# untitled.net
KiCad netlist of a schematic drawn in EAGLE
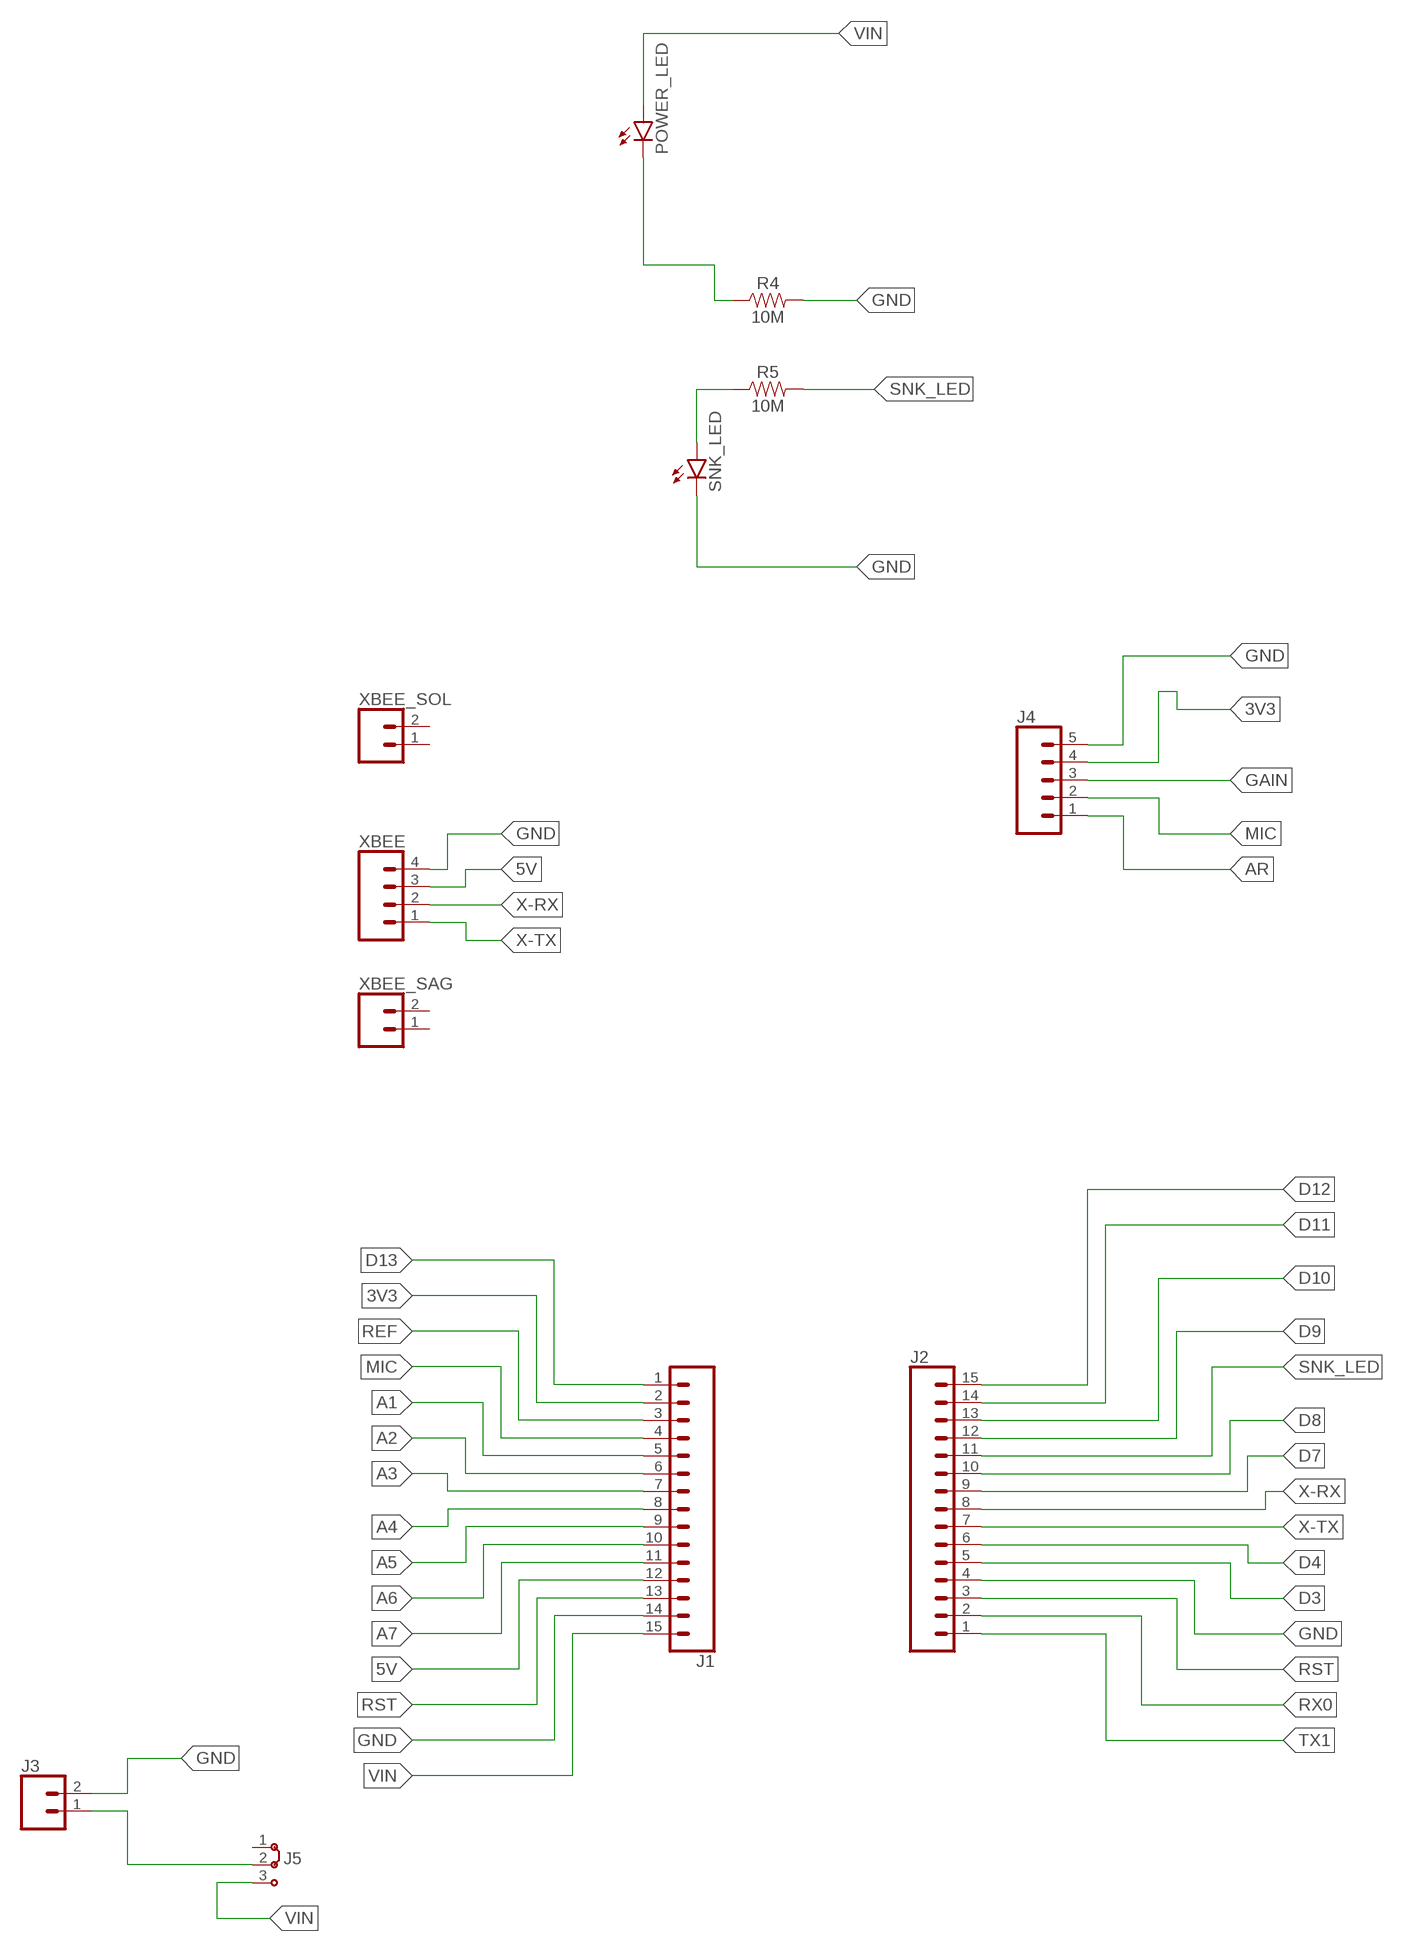
[diagram p0: schematic, sheet 1]

(export (version "E")
  (design (tool "Eeschema 10.0.6"))
  (components
    (comp (ref "J1")
      (value "CONN_15")
      (footprint "eagle-import:1X15")
      (libsource (lib "eagle-import") (part "CONN_15"))
    )
    (comp (ref "J2")
      (value "CONN_15")
      (footprint "eagle-import:1X15")
      (libsource (lib "eagle-import") (part "CONN_15"))
    )
    (comp (ref "J3")
      (value "CONN_025MM")
      (footprint "eagle-import:SCREWTERMINAL-5MM-2")
      (libsource (lib "eagle-import") (part "CONN_025MM"))
    )
    (comp (ref "J4")
      (value "CONN_05")
      (footprint "eagle-import:1X05")
      (libsource (lib "eagle-import") (part "CONN_05"))
    )
    (comp (ref "J5")
      (value "J2X2MM")
      (footprint "eagle-import:04C")
      (libsource (lib "eagle-import") (part "J2X2MM"))
    )
    (comp (ref "POWER_LED")
      (value "LED5MM")
      (footprint "eagle-import:LED5MM")
      (libsource (lib "eagle-import") (part "LED5MM"))
    )
    (comp (ref "R4")
      (value "10M")
      (footprint "eagle-import:AXIAL-0.3")
      (libsource (lib "eagle-import") (part "10MOHM-HORIZ-1/4W-5%"))
    )
    (comp (ref "R5")
      (value "10M")
      (footprint "eagle-import:AXIAL-0.3")
      (libsource (lib "eagle-import") (part "10MOHM-HORIZ-1/4W-5%"))
    )
    (comp (ref "SNK_LED")
      (value "LED5MM")
      (footprint "eagle-import:LED5MM")
      (libsource (lib "eagle-import") (part "LED5MM"))
    )
    (comp (ref "XBEE")
      (value "CONN_04")
      (footprint "eagle-import:1X04")
      (libsource (lib "eagle-import") (part "CONN_04"))
    )
    (comp (ref "XBEE_SAG")
      (value "CONN_02")
      (footprint "eagle-import:1X02")
      (libsource (lib "eagle-import") (part "CONN_02"))
    )
    (comp (ref "XBEE_SOL")
      (value "CONN_02")
      (footprint "eagle-import:1X02")
      (libsource (lib "eagle-import") (part "CONN_02"))
    )
  )
  (nets
    (net (code "1") (name "3V3") (class "Default")
      (node (ref "J1") (pin "2") (pinfunction "2_2") (pintype "passive"))
      (node (ref "J4") (pin "4") (pinfunction "4_4") (pintype "passive"))
    )
    (net (code "2") (name "5V") (class "Default")
      (node (ref "J1") (pin "12") (pinfunction "12_12") (pintype "passive"))
      (node (ref "XBEE") (pin "3") (pinfunction "3_3") (pintype "passive"))
    )
    (net (code "3") (name "A1") (class "Default")
      (node (ref "J1") (pin "5") (pinfunction "5_5") (pintype "passive"))
    )
    (net (code "4") (name "A2") (class "Default")
      (node (ref "J1") (pin "6") (pinfunction "6_6") (pintype "passive"))
    )
    (net (code "5") (name "A3") (class "Default")
      (node (ref "J1") (pin "7") (pinfunction "7_7") (pintype "passive"))
    )
    (net (code "6") (name "A4") (class "Default")
      (node (ref "J1") (pin "8") (pinfunction "8_8") (pintype "passive"))
    )
    (net (code "7") (name "A5") (class "Default")
      (node (ref "J1") (pin "9") (pinfunction "9_9") (pintype "passive"))
    )
    (net (code "8") (name "A6") (class "Default")
      (node (ref "J1") (pin "10") (pinfunction "10_10") (pintype "passive"))
    )
    (net (code "9") (name "A7") (class "Default")
      (node (ref "J1") (pin "11") (pinfunction "11_11") (pintype "passive"))
    )
    (net (code "10") (name "AR") (class "Default")
      (node (ref "J4") (pin "1") (pinfunction "1_1") (pintype "passive"))
    )
    (net (code "11") (name "D3") (class "Default")
      (node (ref "J2") (pin "5") (pinfunction "5_5") (pintype "passive"))
    )
    (net (code "12") (name "D4") (class "Default")
      (node (ref "J2") (pin "6") (pinfunction "6_6") (pintype "passive"))
    )
    (net (code "13") (name "D7") (class "Default")
      (node (ref "J2") (pin "9") (pinfunction "9_9") (pintype "passive"))
    )
    (net (code "14") (name "D8") (class "Default")
      (node (ref "J2") (pin "10") (pinfunction "10_10") (pintype "passive"))
    )
    (net (code "15") (name "D9") (class "Default")
      (node (ref "J2") (pin "12") (pinfunction "12_12") (pintype "passive"))
    )
    (net (code "16") (name "D10") (class "Default")
      (node (ref "J2") (pin "13") (pinfunction "13_13") (pintype "passive"))
    )
    (net (code "17") (name "D11") (class "Default")
      (node (ref "J2") (pin "14") (pinfunction "14_14") (pintype "passive"))
    )
    (net (code "18") (name "D12") (class "Default")
      (node (ref "J2") (pin "15") (pinfunction "15_15") (pintype "passive"))
    )
    (net (code "19") (name "D13") (class "Default")
      (node (ref "J1") (pin "1") (pinfunction "1_1") (pintype "passive"))
    )
    (net (code "20") (name "GAIN") (class "Default")
      (node (ref "J4") (pin "3") (pinfunction "3_3") (pintype "passive"))
    )
    (net (code "21") (name "GND") (class "Default")
      (node (ref "J1") (pin "14") (pinfunction "14_14") (pintype "passive"))
      (node (ref "J2") (pin "4") (pinfunction "4_4") (pintype "passive"))
      (node (ref "J3") (pin "2") (pinfunction "2_2") (pintype "passive"))
      (node (ref "J4") (pin "5") (pinfunction "5_5") (pintype "passive"))
      (node (ref "R4") (pin "P$2") (pinfunction "2_P$2") (pintype "passive"))
      (node (ref "SNK_LED") (pin "K") (pinfunction "C_K") (pintype "passive"))
      (node (ref "XBEE") (pin "4") (pinfunction "4_4") (pintype "passive"))
    )
    (net (code "22") (name "MIC") (class "Default")
      (node (ref "J1") (pin "4") (pinfunction "4_4") (pintype "passive"))
      (node (ref "J4") (pin "2") (pinfunction "2_2") (pintype "passive"))
    )
    (net (code "23") (name "Net-(J3-Pad1)") (class "Default")
      (node (ref "J3") (pin "1") (pinfunction "1_1") (pintype "passive"))
      (node (ref "J5") (pin "2") (pinfunction "2_2") (pintype "passive"))
    )
    (net (code "24") (name "Net-(POWER_LED-C)") (class "Default")
      (node (ref "POWER_LED") (pin "K") (pinfunction "C_K") (pintype "passive"))
      (node (ref "R4") (pin "P$1") (pinfunction "1_P$1") (pintype "passive"))
    )
    (net (code "25") (name "Net-(R5-1)") (class "Default")
      (node (ref "R5") (pin "P$1") (pinfunction "1_P$1") (pintype "passive"))
      (node (ref "SNK_LED") (pin "A") (pinfunction "A_A") (pintype "passive"))
    )
    (net (code "26") (name "REF") (class "Default")
      (node (ref "J1") (pin "3") (pinfunction "3_3") (pintype "passive"))
    )
    (net (code "27") (name "RST") (class "Default")
      (node (ref "J1") (pin "13") (pinfunction "13_13") (pintype "passive"))
      (node (ref "J2") (pin "3") (pinfunction "3_3") (pintype "passive"))
    )
    (net (code "28") (name "RX0") (class "Default")
      (node (ref "J2") (pin "2") (pinfunction "2_2") (pintype "passive"))
    )
    (net (code "29") (name "SNK_LED") (class "Default")
      (node (ref "J2") (pin "11") (pinfunction "11_11") (pintype "passive"))
      (node (ref "R5") (pin "P$2") (pinfunction "2_P$2") (pintype "passive"))
    )
    (net (code "30") (name "TX1") (class "Default")
      (node (ref "J2") (pin "1") (pinfunction "1_1") (pintype "passive"))
    )
    (net (code "31") (name "VIN") (class "Default")
      (node (ref "J1") (pin "15") (pinfunction "15_15") (pintype "passive"))
      (node (ref "J5") (pin "3") (pinfunction "3_3") (pintype "passive"))
      (node (ref "POWER_LED") (pin "A") (pinfunction "A_A") (pintype "passive"))
    )
    (net (code "32") (name "X-RX") (class "Default")
      (node (ref "J2") (pin "8") (pinfunction "8_8") (pintype "passive"))
      (node (ref "XBEE") (pin "2") (pinfunction "2_2") (pintype "passive"))
    )
    (net (code "33") (name "X-TX") (class "Default")
      (node (ref "J2") (pin "7") (pinfunction "7_7") (pintype "passive"))
      (node (ref "XBEE") (pin "1") (pinfunction "1_1") (pintype "passive"))
    )
    (net (code "34") (name "unconnected-(J5-Pad1)") (class "Default")
      (node (ref "J5") (pin "1") (pinfunction "1_1") (pintype "passive"))
    )
    (net (code "35") (name "unconnected-(XBEE_SAG-Pad1)") (class "Default")
      (node (ref "XBEE_SAG") (pin "1") (pinfunction "1_1") (pintype "passive"))
    )
    (net (code "36") (name "unconnected-(XBEE_SAG-Pad2)") (class "Default")
      (node (ref "XBEE_SAG") (pin "2") (pinfunction "2_2") (pintype "passive"))
    )
    (net (code "37") (name "unconnected-(XBEE_SOL-Pad1)") (class "Default")
      (node (ref "XBEE_SOL") (pin "1") (pinfunction "1_1") (pintype "passive"))
    )
    (net (code "38") (name "unconnected-(XBEE_SOL-Pad2)") (class "Default")
      (node (ref "XBEE_SOL") (pin "2") (pinfunction "2_2") (pintype "passive"))
    )
  )
)
